# DotPhat.net
KiCad netlist of a schematic drawn in EAGLE
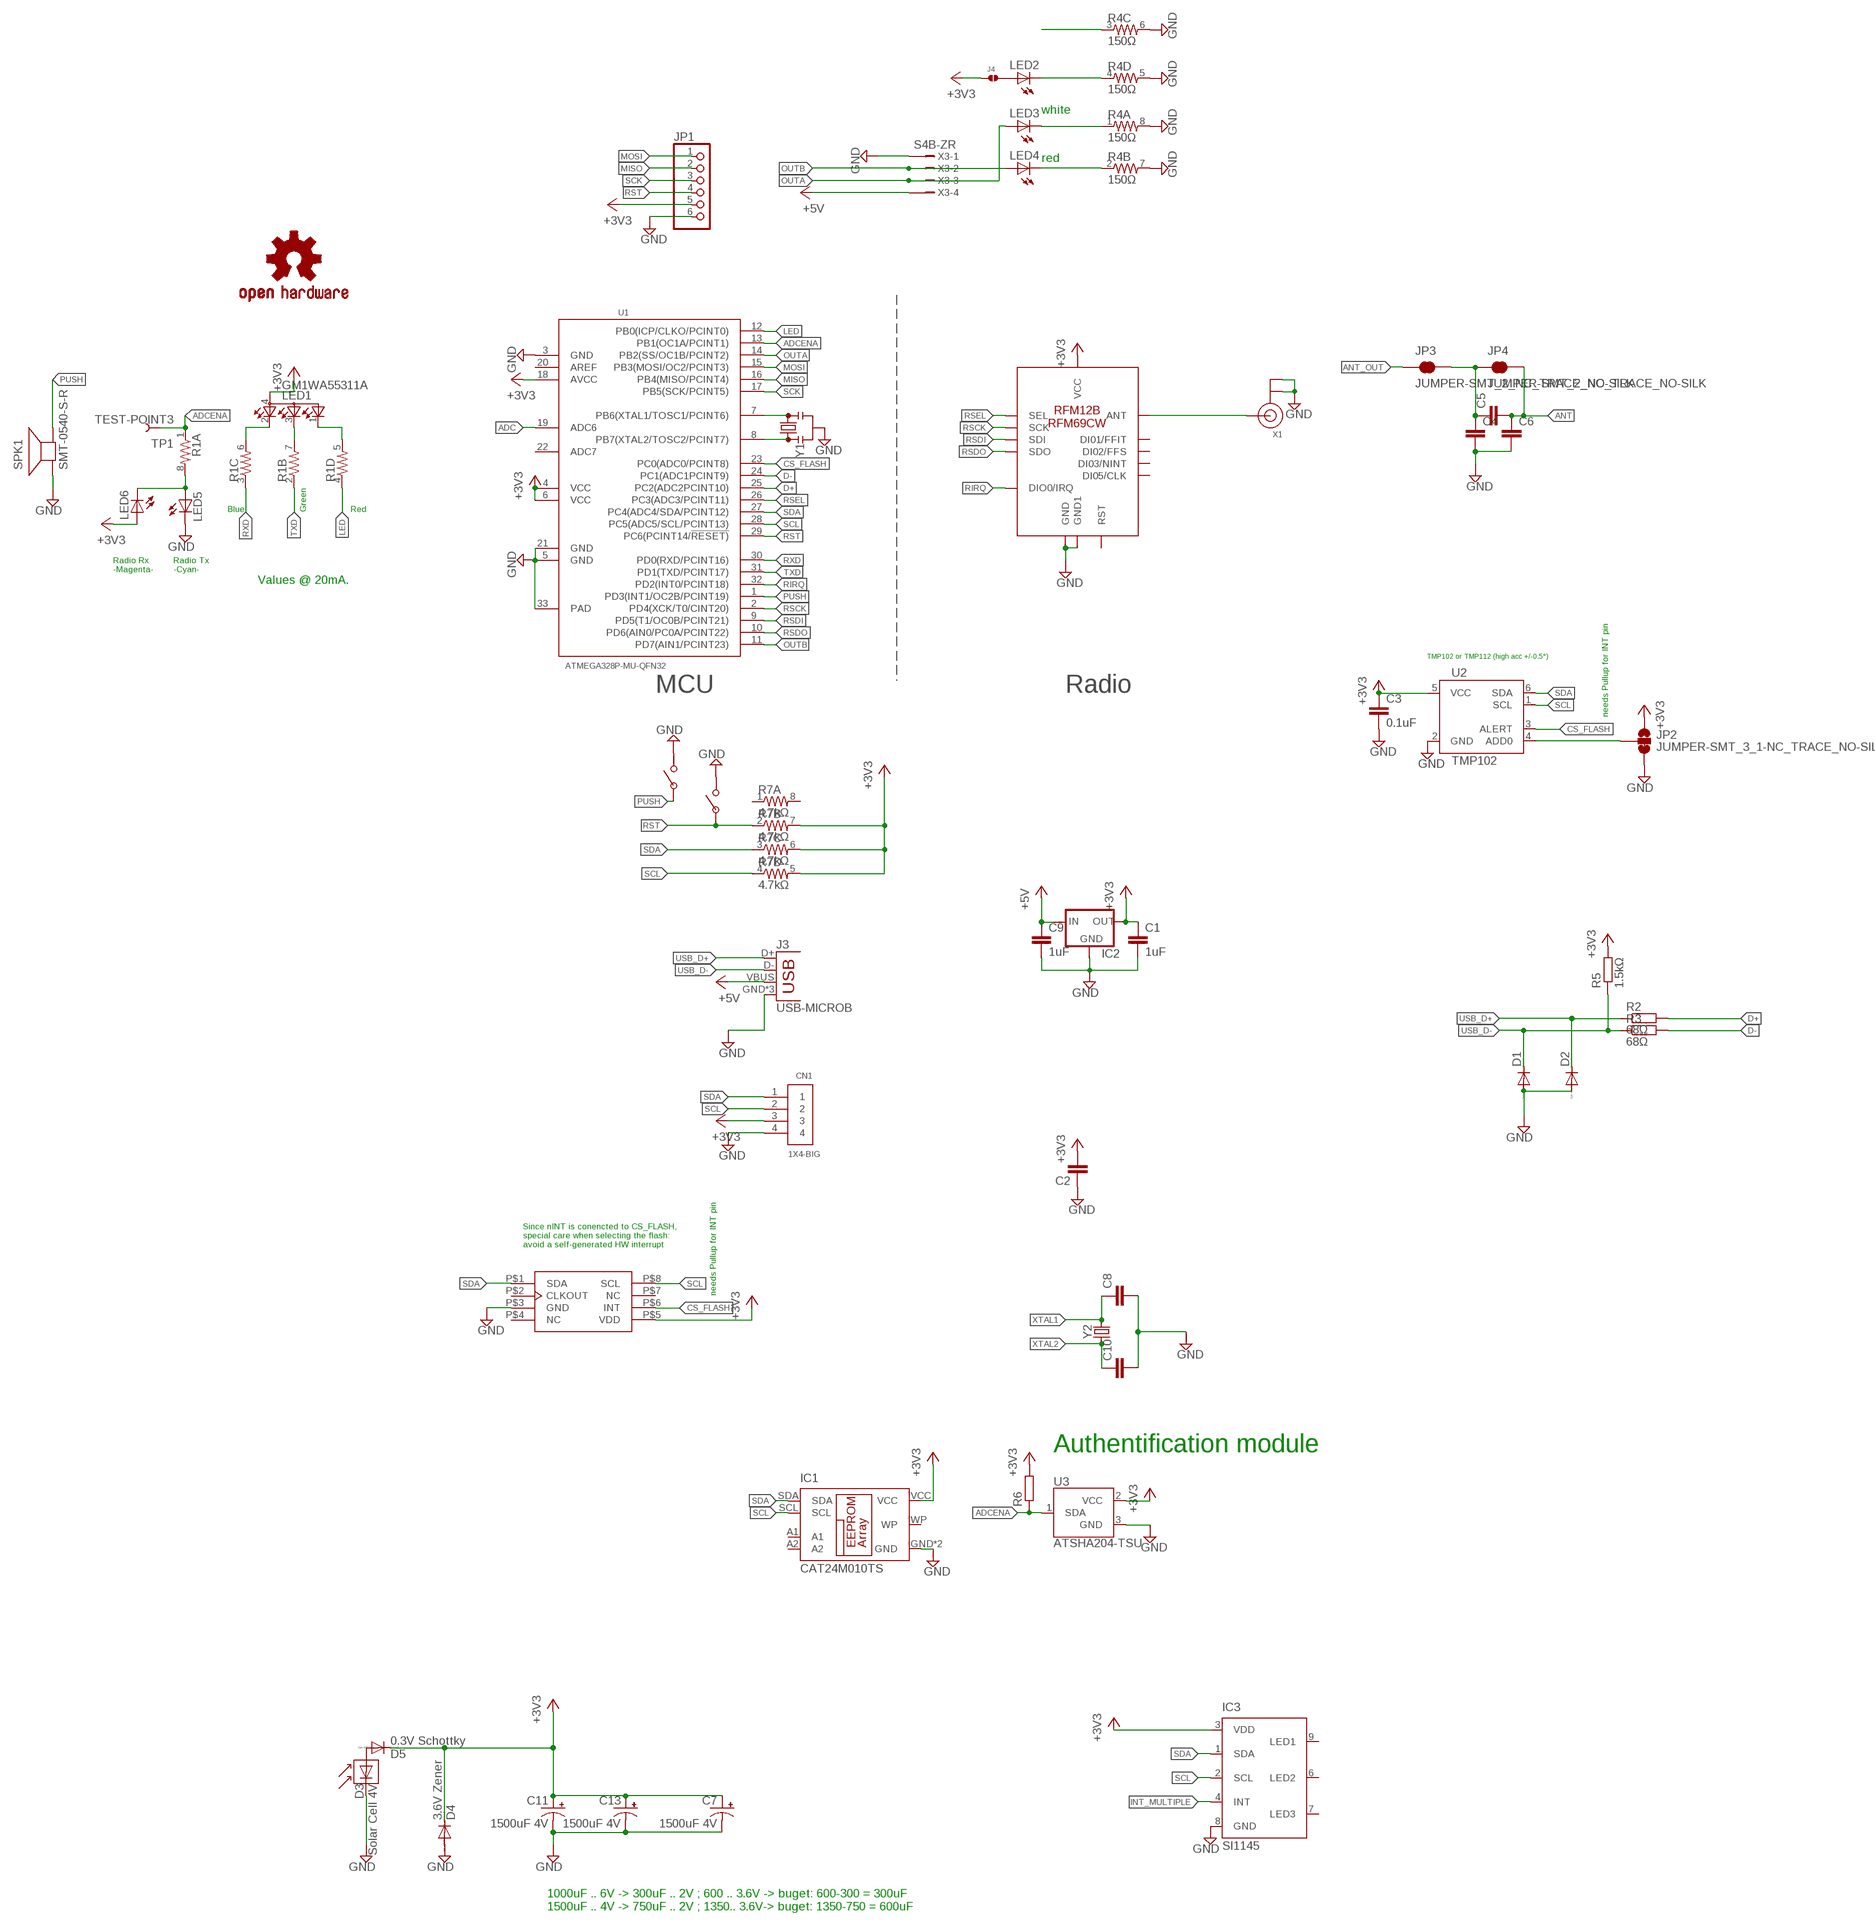
[diagram p0: schematic, sheet 1]

(export (version "E")
  (design (tool "Eeschema 10.0.6"))
  (components
    (comp (ref "C1")
      (value "1uF")
      (footprint "eagle-import:C0603")
      (libsource (lib "eagle-import") (part "C-EUC0603"))
    )
    (comp (ref "C2")
      (value "C-EUC3216")
      (footprint "eagle-import:C3216")
      (libsource (lib "eagle-import") (part "C-EUC3216"))
    )
    (comp (ref "C3")
      (value "0.1uF")
      (footprint "eagle-import:C0603")
      (libsource (lib "eagle-import") (part "resistor_C-EUC0603"))
    )
    (comp (ref "C4")
      (value "C-EUC0603")
      (footprint "eagle-import:C0603")
      (libsource (lib "eagle-import") (part "C-EUC0603"))
    )
    (comp (ref "C5")
      (value "C-EUC0603")
      (footprint "eagle-import:C0603")
      (libsource (lib "eagle-import") (part "C-EUC0603"))
    )
    (comp (ref "C6")
      (value "C-EUC0603")
      (footprint "eagle-import:C0603")
      (libsource (lib "eagle-import") (part "C-EUC0603"))
    )
    (comp (ref "C7")
      (value "1500uF 4V")
      (footprint "eagle-import:CT7343")
      (libsource (lib "eagle-import") (part "CPOL-USCT7343"))
    )
    (comp (ref "C8")
      (value "C-EUC0402")
      (footprint "eagle-import:C0402")
      (libsource (lib "eagle-import") (part "C-EUC0402"))
    )
    (comp (ref "C9")
      (value "1uF")
      (footprint "eagle-import:C0603")
      (libsource (lib "eagle-import") (part "C-EUC0603"))
    )
    (comp (ref "C10")
      (value "C-EUC0402")
      (footprint "eagle-import:C0402")
      (libsource (lib "eagle-import") (part "C-EUC0402"))
    )
    (comp (ref "C11")
      (value "1500uF 4V")
      (footprint "eagle-import:CT7343")
      (libsource (lib "eagle-import") (part "CPOL-USCT7343"))
    )
    (comp (ref "C13")
      (value "1500uF 4V")
      (footprint "eagle-import:CT7343")
      (libsource (lib "eagle-import") (part "CPOL-USCT7343"))
    )
    (comp (ref "CN1")
      (value "1X4-BIG")
      (footprint "eagle-import:1X04-BIG")
      (libsource (lib "eagle-import") (part "1X4-BIG"))
    )
    (comp (ref "D1")
      (value "DIODE-SOD523")
      (footprint "eagle-import:SOD523")
      (libsource (lib "eagle-import") (part "DIODE-SOD523"))
    )
    (comp (ref "D2")
      (value "DIODE-SOD523")
      (footprint "eagle-import:SOD523")
      (libsource (lib "eagle-import") (part "DIODE-SOD523"))
    )
    (comp (ref "D3")
      (value "Solar Cell 4V")
      (footprint "eagle-import:SOLARBIT-12X1")
      (libsource (lib "eagle-import") (part "SOLAR-IXYS-"))
    )
    (comp (ref "D4")
      (value "3.6V Zener")
      (footprint "eagle-import:SOD523")
      (libsource (lib "eagle-import") (part "DIODE-SOD523"))
    )
    (comp (ref "D5")
      (value "0.3V Schottky")
      (footprint "eagle-import:SOD523")
      (libsource (lib "eagle-import") (part "DIODE-SOD523"))
    )
    (comp (ref "IC1")
      (value "CAT24M010TS")
      (footprint "eagle-import:TSSOP8")
      (fields (field (name "MF") "On Semiconductor") (field (name "MPN") "24C00T-E/ST"))
      (libsource (lib "eagle-import") (part "CAT24M01TS0"))
    )
    (comp (ref "IC2")
      (value "MCP1700TT")
      (footprint "eagle-import:SOT-23")
      (libsource (lib "eagle-import") (part "MCP1700TT"))
    )
    (comp (ref "IC3")
      (value "SI1145")
      (footprint "eagle-import:QFN-10")
      (libsource (lib "eagle-import") (part "SI1145"))
    )
    (comp (ref "J3")
      (value "USB-MICROB")
      (footprint "eagle-import:USB-MICROB")
      (libsource (lib "eagle-import") (part "USB-MICROB"))
    )
    (comp (ref "J4")
      (value "SOLDERJUMPER.2.MED")
      (footprint "eagle-import:2.MED")
      (libsource (lib "eagle-import") (part "SOLDERJUMPER.2.MED"))
    )
    (comp (ref "JP1")
      (value "PINHD-1X6")
      (footprint "eagle-import:1X06")
      (libsource (lib "eagle-import") (part "PINHD-1X6"))
    )
    (comp (ref "JP2")
      (value "JUMPER-SMT_3_1-NC_TRACE_NO-SILK")
      (footprint "eagle-import:SMT-JUMPER_3_1-NC_TRACE_NO-SILK")
      (libsource (lib "eagle-import") (part "JUMPER-SMT_3_1-NC_TRACE_NO-SILK"))
    )
    (comp (ref "JP3")
      (value "JUMPER-SMT_2_NC_TRACE_NO-SILK")
      (footprint "eagle-import:SMT-JUMPER_2_NC_TRACE_NO-SILK")
      (libsource (lib "eagle-import") (part "JUMPER-SMT_2_NC_TRACE_NO-SILK"))
    )
    (comp (ref "JP4")
      (value "JUMPER-SMT_2_NC_TRACE_NO-SILK")
      (footprint "eagle-import:SMT-JUMPER_2_NC_TRACE_NO-SILK")
      (libsource (lib "eagle-import") (part "JUMPER-SMT_2_NC_TRACE_NO-SILK"))
    )
    (comp (ref "LED1")
      (value "GM1WA55311A")
      (footprint "eagle-import:GM1WA55311A")
      (libsource (lib "eagle-import") (part "GM1WA55311A"))
    )
    (comp (ref "LED2")
      (value "LED0603")
      (footprint "eagle-import:LED-0603")
      (libsource (lib "eagle-import") (part "LED0603"))
    )
    (comp (ref "LED3")
      (value "LED0603")
      (footprint "eagle-import:LED-0603")
      (libsource (lib "eagle-import") (part "LED0603"))
    )
    (comp (ref "LED4")
      (value "LED0603")
      (footprint "eagle-import:LED-0603")
      (libsource (lib "eagle-import") (part "LED0603"))
    )
    (comp (ref "LED5")
      (value "LED0603")
      (footprint "eagle-import:LED-0603")
      (libsource (lib "eagle-import") (part "LED0603"))
    )
    (comp (ref "LED6")
      (value "LED0603")
      (footprint "eagle-import:LED-0603")
      (libsource (lib "eagle-import") (part "LED0603"))
    )
    (comp (ref "LOGO1")
      (value "OSHW-LOGOS")
      (footprint "eagle-import:OSHW-LOGO-S")
      (libsource (lib "eagle-import") (part "OSHW-LOGOS"))
    )
    (comp (ref "R1")
      (value "RESISTOR-ARRAY0603-ARV")
      (footprint "eagle-import:0603-ARV")
      (libsource (lib "eagle-import") (part "RESISTOR-ARRAY0603-ARV"))
    )
    (comp (ref "R2")
      (value "68Ω")
      (footprint "eagle-import:R0603")
      (libsource (lib "eagle-import") (part "R-EU_R0603"))
    )
    (comp (ref "R3")
      (value "68Ω")
      (footprint "eagle-import:R0603")
      (libsource (lib "eagle-import") (part "R-EU_R0603"))
    )
    (comp (ref "R4")
      (value "150Ω")
      (footprint "eagle-import:0603-ARV")
      (libsource (lib "eagle-import") (part "RESISTOR-ARRAY0603-ARV"))
    )
    (comp (ref "R5")
      (value "1.5kΩ")
      (footprint "eagle-import:R0603")
      (libsource (lib "eagle-import") (part "R-EU_R0603"))
    )
    (comp (ref "R6")
      (value "R-EU_R0603")
      (footprint "eagle-import:R0603")
      (libsource (lib "eagle-import") (part "R-EU_R0603"))
    )
    (comp (ref "R7")
      (value "4.7kΩ")
      (footprint "eagle-import:0603-ARV")
      (libsource (lib "eagle-import") (part "RESISTOR-ARRAY0603-ARV"))
    )
    (comp (ref "SPK1")
      (value "SMT-0540-S-R")
      (footprint "eagle-import:SMT-0540-S-R")
      (libsource (lib "eagle-import") (part "SMT-0540-S-R"))
    )
    (comp (ref "TP1")
      (value "TEST-POINT3")
      (footprint "eagle-import:PAD.03X.03")
      (libsource (lib "eagle-import") (part "TEST-POINT3"))
    )
    (comp (ref "U$1")
      (value "RFM12B/69CW")
      (footprint "eagle-import:RFM12B_69CW")
      (libsource (lib "eagle-import") (part "RFM12B/69CW"))
    )
    (comp (ref "U$2")
      (value "PUSHBUTTON_4X2.5")
      (footprint "eagle-import:PUSHBUTTON_4X2.5")
      (libsource (lib "eagle-import") (part "PUSHBUTTON_4X2.5"))
    )
    (comp (ref "U$3")
      (value "PUSHBUTTON_4X2.5")
      (footprint "eagle-import:PUSHBUTTON_4X2.5")
      (libsource (lib "eagle-import") (part "PUSHBUTTON_4X2.5"))
    )
    (comp (ref "U1")
      (value "ATMEGA328P-MU-QFN32")
      (footprint "eagle-import:QFN32G-0.5-5X5MM")
      (fields (field (name "MPN") "ATMEGA328P-MU"))
      (libsource (lib "eagle-import") (part "MCU-ATMEGA328P-MU(QFN32)"))
    )
    (comp (ref "U2")
      (value "TMP102")
      (footprint "eagle-import:SOT563")
      (libsource (lib "eagle-import") (part "TMP102"))
    )
    (comp (ref "U3")
      (value "ATSHA204-TSU")
      (footprint "eagle-import:SOT23-3")
      (libsource (lib "eagle-import") (part "ATSHA204-TSU"))
    )
    (comp (ref "X1")
      (value "ANTENNA_U.FL")
      (footprint "eagle-import:U.FL")
      (libsource (lib "eagle-import") (part "ANTENNA_U.FL"))
    )
    (comp (ref "X2")
      (value "MC-RTC-RV-4162-C7-I2C")
      (footprint "eagle-import:MC-RTC-C7")
      (libsource (lib "eagle-import") (part "MC-RTC-RV-4162-C7-I2C"))
    )
    (comp (ref "X3")
      (value "S4B-ZR")
      (footprint "eagle-import:S4B-ZR")
      (fields (field (name "MF") "FARNELL") (field (name "MPN") "S4B-ZR(LF)(SN)"))
      (libsource (lib "eagle-import") (part "?4B-ZRS"))
    )
    (comp (ref "Y1")
      (value "RESONATORSMD-3.2X1.3")
      (footprint "eagle-import:RESONATOR-SMD-3.2X1.3")
      (libsource (lib "eagle-import") (part "RESONATORSMD-3.2X1.3"))
    )
    (comp (ref "Y2")
      (value "CRYSTALSMD-3.2X1.5")
      (footprint "eagle-import:CRYSTAL-SMD-3.2X1.5MM")
      (libsource (lib "eagle-import") (part "CRYSTALSMD-3.2X1.5"))
    )
  )
  (nets
    (net (code "1") (name "+3V3") (class "Default")
      (node (ref "C1") (pin "1") (pinfunction "1_1") (pintype "passive"))
      (node (ref "C11") (pin "+") (pinfunction "+_+") (pintype "passive"))
      (node (ref "C13") (pin "+") (pinfunction "+_+") (pintype "passive"))
      (node (ref "C2") (pin "2") (pinfunction "2_2") (pintype "passive"))
      (node (ref "C3") (pin "1") (pinfunction "1_1") (pintype "passive"))
      (node (ref "C7") (pin "+") (pinfunction "+_+") (pintype "passive"))
      (node (ref "CN1") (pin "3") (pinfunction "3_3") (pintype "bidirectional"))
      (node (ref "D4") (pin "C") (pinfunction "C_C") (pintype "passive"))
      (node (ref "D5") (pin "C") (pinfunction "C_C") (pintype "passive"))
      (node (ref "IC1") (pin "VCC") (pinfunction "VCC_VCC") (pintype "power_in"))
      (node (ref "IC2") (pin "2") (pinfunction "OUT_2") (pintype "passive"))
      (node (ref "IC3") (pin "3") (pinfunction "VDD_3") (pintype "power_in"))
      (node (ref "J4") (pin "1") (pinfunction "1_1") (pintype "bidirectional"))
      (node (ref "JP1") (pin "5") (pinfunction "5_5") (pintype "passive"))
      (node (ref "JP2") (pin "1") (pinfunction "1_1") (pintype "passive"))
      (node (ref "LED1") (pin "4") (pinfunction "A_4") (pintype "passive"))
      (node (ref "LED6") (pin "A") (pinfunction "A_A") (pintype "passive"))
      (node (ref "R5") (pin "2") (pinfunction "2_2") (pintype "passive"))
      (node (ref "R6") (pin "2") (pinfunction "2_2") (pintype "passive"))
      (node (ref "R7") (pin "5") (pinfunction "2_5") (pintype "passive"))
      (node (ref "R7") (pin "6") (pinfunction "2_6") (pintype "passive"))
      (node (ref "R7") (pin "7") (pinfunction "2_7") (pintype "passive"))
      (node (ref "U$1") (pin "VDD") (pinfunction "VCC_VDD") (pintype "power_in"))
      (node (ref "U1") (pin "18") (pinfunction "AVCC_18") (pintype "bidirectional"))
      (node (ref "U1") (pin "4") (pinfunction "VCC_4") (pintype "bidirectional"))
      (node (ref "U1") (pin "6") (pinfunction "VCC_6") (pintype "bidirectional"))
      (node (ref "U2") (pin "5") (pinfunction "VCC_5") (pintype "bidirectional"))
      (node (ref "U3") (pin "2") (pinfunction "VCC_2") (pintype "bidirectional"))
      (node (ref "X2") (pin "P$5") (pinfunction "VDD_P$5") (pintype "power_in"))
    )
    (net (code "2") (name "+5V") (class "Default")
      (node (ref "C9") (pin "1") (pinfunction "1_1") (pintype "passive"))
      (node (ref "IC2") (pin "3") (pinfunction "IN_3") (pintype "input"))
      (node (ref "J3") (pin "VBUS") (pinfunction "VBUS_VBUS") (pintype "bidirectional"))
      (node (ref "X3") (pin "4") (pinfunction "1_4") (pintype "passive"))
    )
    (net (code "3") (name "ADC") (class "Default")
      (node (ref "U1") (pin "19") (pinfunction "ADC6_19") (pintype "bidirectional"))
    )
    (net (code "4") (name "ADCENA") (class "Default")
      (node (ref "R1") (pin "1") (pinfunction "1_1") (pintype "passive"))
      (node (ref "R6") (pin "1") (pinfunction "1_1") (pintype "passive"))
      (node (ref "TP1") (pin "P$1") (pinfunction "1_P$1") (pintype "bidirectional"))
      (node (ref "U1") (pin "13") (pinfunction "PB1(OC1A/PCINT1)_13") (pintype "bidirectional"))
      (node (ref "U3") (pin "1") (pinfunction "SDA_1") (pintype "bidirectional"))
    )
    (net (code "5") (name "ANT") (class "Default")
      (node (ref "C5") (pin "2") (pinfunction "2_2") (pintype "passive"))
      (node (ref "C6") (pin "1") (pinfunction "1_1") (pintype "passive"))
      (node (ref "JP4") (pin "2") (pinfunction "2_2") (pintype "passive"))
    )
    (net (code "6") (name "ANT_OUT") (class "Default")
      (node (ref "JP3") (pin "1") (pinfunction "1_1") (pintype "passive"))
      (node (ref "U$1") (pin "ANT") (pinfunction "ANT_ANT") (pintype "passive"))
      (node (ref "X1") (pin "3") (pinfunction "SIGNAL_3") (pintype "passive"))
    )
    (net (code "7") (name "CS_FLASH") (class "Default")
      (node (ref "U1") (pin "23") (pinfunction "PC0(ADC0/PCINT8)_23") (pintype "bidirectional"))
      (node (ref "U2") (pin "3") (pinfunction "ALERT_3") (pintype "bidirectional"))
      (node (ref "X2") (pin "P$6") (pinfunction "INT_P$6") (pintype "bidirectional"))
    )
    (net (code "8") (name "D+") (class "Default")
      (node (ref "R2") (pin "2") (pinfunction "2_2") (pintype "passive"))
      (node (ref "U1") (pin "25") (pinfunction "PC2(ADC2PCINT10)_25") (pintype "bidirectional"))
    )
    (net (code "9") (name "D-") (class "Default")
      (node (ref "R3") (pin "2") (pinfunction "2_2") (pintype "passive"))
      (node (ref "U1") (pin "24") (pinfunction "PC1(ADC1PCINT9)_24") (pintype "bidirectional"))
    )
    (net (code "10") (name "GND") (class "Default")
      (node (ref "C1") (pin "2") (pinfunction "2_2") (pintype "passive"))
      (node (ref "C10") (pin "2") (pinfunction "2_2") (pintype "passive"))
      (node (ref "C11") (pin "-") (pinfunction "-_-") (pintype "passive"))
      (node (ref "C13") (pin "-") (pinfunction "-_-") (pintype "passive"))
      (node (ref "C2") (pin "1") (pinfunction "1_1") (pintype "passive"))
      (node (ref "C3") (pin "2") (pinfunction "2_2") (pintype "passive"))
      (node (ref "C4") (pin "2") (pinfunction "2_2") (pintype "passive"))
      (node (ref "C6") (pin "2") (pinfunction "2_2") (pintype "passive"))
      (node (ref "C7") (pin "-") (pinfunction "-_-") (pintype "passive"))
      (node (ref "C8") (pin "2") (pinfunction "2_2") (pintype "passive"))
      (node (ref "C9") (pin "2") (pinfunction "2_2") (pintype "passive"))
      (node (ref "CN1") (pin "4") (pinfunction "4_4") (pintype "bidirectional"))
      (node (ref "D1") (pin "A") (pinfunction "A_A") (pintype "passive"))
      (node (ref "D2") (pin "A") (pinfunction "A_A") (pintype "passive"))
      (node (ref "D3") (pin "-") (pinfunction "C_-") (pintype "passive"))
      (node (ref "D4") (pin "A") (pinfunction "A_A") (pintype "passive"))
      (node (ref "IC1") (pin "GND") (pinfunction "GND_GND") (pintype "power_in"))
      (node (ref "IC1") (pin "NC") (pinfunction "GND_NC") (pintype "power_in"))
      (node (ref "IC2") (pin "1") (pinfunction "GND_1") (pintype "input"))
      (node (ref "IC3") (pin "8") (pinfunction "GND_8") (pintype "power_in"))
      (node (ref "J3") (pin "GND") (pinfunction "GND_GND") (pintype "bidirectional"))
      (node (ref "J3") (pin "MT1") (pinfunction "GND_MT1") (pintype "bidirectional"))
      (node (ref "J3") (pin "MT2") (pinfunction "GND_MT2") (pintype "bidirectional"))
      (node (ref "JP1") (pin "6") (pinfunction "6_6") (pintype "passive"))
      (node (ref "JP2") (pin "3") (pinfunction "3_3") (pintype "passive"))
      (node (ref "LED5") (pin "C") (pinfunction "C_C") (pintype "passive"))
      (node (ref "R4") (pin "5") (pinfunction "2_5") (pintype "passive"))
      (node (ref "R4") (pin "6") (pinfunction "2_6") (pintype "passive"))
      (node (ref "R4") (pin "7") (pinfunction "2_7") (pintype "passive"))
      (node (ref "R4") (pin "8") (pinfunction "2_8") (pintype "passive"))
      (node (ref "SPK1") (pin "-") (pinfunction "+_-") (pintype "passive"))
      (node (ref "U$1") (pin "GND") (pinfunction "GND_GND") (pintype "power_in"))
      (node (ref "U$1") (pin "GND1") (pinfunction "GND1_GND1") (pintype "power_in"))
      (node (ref "U$2") (pin "P$2") (pinfunction "P$2_P$2") (pintype "bidirectional"))
      (node (ref "U$3") (pin "P$2") (pinfunction "P$2_P$2") (pintype "bidirectional"))
      (node (ref "U1") (pin "21") (pinfunction "GND_21") (pintype "bidirectional"))
      (node (ref "U1") (pin "3") (pinfunction "GND_3") (pintype "bidirectional"))
      (node (ref "U1") (pin "33") (pinfunction "PAD_33") (pintype "bidirectional"))
      (node (ref "U1") (pin "5") (pinfunction "GND_5") (pintype "bidirectional"))
      (node (ref "U2") (pin "2") (pinfunction "GND_2") (pintype "bidirectional"))
      (node (ref "U3") (pin "3") (pinfunction "GND_3") (pintype "bidirectional"))
      (node (ref "X1") (pin "1") (pinfunction "GND_1") (pintype "passive"))
      (node (ref "X1") (pin "2") (pinfunction "GND_2") (pintype "passive"))
      (node (ref "X2") (pin "P$3") (pinfunction "GND_P$3") (pintype "power_in"))
      (node (ref "X3") (pin "1") (pinfunction "1_1") (pintype "passive"))
      (node (ref "Y1") (pin "2") (pinfunction "2_2") (pintype "passive"))
    )
    (net (code "11") (name "INT_MULTIPLE") (class "Default")
      (node (ref "IC3") (pin "4") (pinfunction "INT_4") (pintype "open_collector"))
    )
    (net (code "12") (name "LED") (class "Default")
      (node (ref "R1") (pin "4") (pinfunction "1_4") (pintype "passive"))
      (node (ref "U1") (pin "12") (pinfunction "PB0(ICP/CLKO/PCINT0)_12") (pintype "bidirectional"))
    )
    (net (code "13") (name "MISO") (class "Default")
      (node (ref "JP1") (pin "2") (pinfunction "2_2") (pintype "passive"))
      (node (ref "U1") (pin "16") (pinfunction "PB4(MISO/PCINT4)_16") (pintype "bidirectional"))
    )
    (net (code "14") (name "MOSI") (class "Default")
      (node (ref "JP1") (pin "1") (pinfunction "1_1") (pintype "passive"))
      (node (ref "U1") (pin "15") (pinfunction "PB3(MOSI/OC2/PCINT3)_15") (pintype "bidirectional"))
    )
    (net (code "15") (name "Net-(C4-Pad1)") (class "Default")
      (node (ref "C4") (pin "1") (pinfunction "1_1") (pintype "passive"))
      (node (ref "C5") (pin "1") (pinfunction "1_1") (pintype "passive"))
      (node (ref "JP3") (pin "2") (pinfunction "2_2") (pintype "passive"))
      (node (ref "JP4") (pin "1") (pinfunction "1_1") (pintype "passive"))
    )
    (net (code "16") (name "Net-(D3-A)") (class "Default")
      (node (ref "D3") (pin "+") (pinfunction "A_+") (pintype "passive"))
      (node (ref "D5") (pin "A") (pinfunction "A_A") (pintype "passive"))
    )
    (net (code "17") (name "Net-(J4-Pad2)") (class "Default")
      (node (ref "J4") (pin "2") (pinfunction "2_2") (pintype "bidirectional"))
      (node (ref "LED2") (pin "A") (pinfunction "A_A") (pintype "passive"))
    )
    (net (code "18") (name "Net-(LED1-CBLUE)") (class "Default")
      (node (ref "LED1") (pin "3") (pinfunction "CBLUE_3") (pintype "passive"))
      (node (ref "R1") (pin "7") (pinfunction "2_7") (pintype "passive"))
    )
    (net (code "19") (name "Net-(LED1-CGREEN)") (class "Default")
      (node (ref "LED1") (pin "1") (pinfunction "CGREEN_1") (pintype "passive"))
      (node (ref "R1") (pin "5") (pinfunction "2_5") (pintype "passive"))
    )
    (net (code "20") (name "Net-(LED1-CRED)") (class "Default")
      (node (ref "LED1") (pin "2") (pinfunction "CRED_2") (pintype "passive"))
      (node (ref "R1") (pin "6") (pinfunction "2_6") (pintype "passive"))
    )
    (net (code "21") (name "Net-(LED3-PadC)") (class "Default")
      (node (ref "LED3") (pin "C") (pinfunction "C_C") (pintype "passive"))
      (node (ref "R4") (pin "1") (pinfunction "1_1") (pintype "passive"))
    )
    (net (code "22") (name "Net-(R1A-2)") (class "Default")
      (node (ref "LED5") (pin "A") (pinfunction "A_A") (pintype "passive"))
      (node (ref "LED6") (pin "C") (pinfunction "C_C") (pintype "passive"))
      (node (ref "R1") (pin "8") (pinfunction "2_8") (pintype "passive"))
    )
    (net (code "23") (name "Net-(R4B-1)") (class "Default")
      (node (ref "LED4") (pin "C") (pinfunction "C_C") (pintype "passive"))
      (node (ref "R4") (pin "2") (pinfunction "1_2") (pintype "passive"))
    )
    (net (code "24") (name "Net-(R4D-1)") (class "Default")
      (node (ref "LED2") (pin "C") (pinfunction "C_C") (pintype "passive"))
      (node (ref "R4") (pin "4") (pinfunction "1_4") (pintype "passive"))
    )
    (net (code "25") (name "Net-(U1-PB6(XTAL1{slash}TOSC1{slash}PCINT6))") (class "Default")
      (node (ref "U1") (pin "7") (pinfunction "PB6(XTAL1/TOSC1/PCINT6)_7") (pintype "bidirectional"))
      (node (ref "Y1") (pin "3") (pinfunction "3_3") (pintype "passive"))
    )
    (net (code "26") (name "Net-(U1-PB7(XTAL2{slash}TOSC2{slash}PCINT7))") (class "Default")
      (node (ref "U1") (pin "8") (pinfunction "PB7(XTAL2/TOSC2/PCINT7)_8") (pintype "bidirectional"))
      (node (ref "Y1") (pin "1") (pinfunction "1_1") (pintype "passive"))
    )
    (net (code "27") (name "Net-(U2-ADD0)") (class "Default")
      (node (ref "JP2") (pin "2") (pinfunction "2_2") (pintype "passive"))
      (node (ref "U2") (pin "4") (pinfunction "ADD0_4") (pintype "bidirectional"))
    )
    (net (code "28") (name "OUTA") (class "Default")
      (node (ref "LED3") (pin "A") (pinfunction "A_A") (pintype "passive"))
      (node (ref "U1") (pin "14") (pinfunction "PB2(SS/OC1B/PCINT2)_14") (pintype "bidirectional"))
      (node (ref "X3") (pin "3") (pinfunction "1_3") (pintype "passive"))
    )
    (net (code "29") (name "OUTB") (class "Default")
      (node (ref "LED4") (pin "A") (pinfunction "A_A") (pintype "passive"))
      (node (ref "U1") (pin "11") (pinfunction "PD7(AIN1/PCINT23)_11") (pintype "bidirectional"))
      (node (ref "X3") (pin "2") (pinfunction "1_2") (pintype "passive"))
    )
    (net (code "30") (name "PUSH") (class "Default")
      (node (ref "SPK1") (pin "+") (pinfunction "-_+") (pintype "passive"))
      (node (ref "U$3") (pin "P$1") (pinfunction "P$1_P$1") (pintype "bidirectional"))
      (node (ref "U1") (pin "1") (pinfunction "PD3(INT1/OC2B/PCINT19)_1") (pintype "bidirectional"))
    )
    (net (code "31") (name "RIRQ") (class "Default")
      (node (ref "U$1") (pin "IRQ") (pinfunction "DIO0/IRQ_IRQ") (pintype "open_collector"))
      (node (ref "U1") (pin "32") (pinfunction "PD2(INT0/PCINT18)_32") (pintype "bidirectional"))
    )
    (net (code "32") (name "RSCK") (class "Default")
      (node (ref "U$1") (pin "SCK") (pinfunction "SCK_SCK") (pintype "input"))
      (node (ref "U1") (pin "2") (pinfunction "PD4(XCK/T0/CINT20)_2") (pintype "bidirectional"))
    )
    (net (code "33") (name "RSDI") (class "Default")
      (node (ref "U$1") (pin "SDI") (pinfunction "SDI_SDI") (pintype "input"))
      (node (ref "U1") (pin "9") (pinfunction "PD5(T1/OC0B/PCINT21)_9") (pintype "bidirectional"))
    )
    (net (code "34") (name "RSDO") (class "Default")
      (node (ref "U$1") (pin "SDO") (pinfunction "SDO_SDO") (pintype "output"))
      (node (ref "U1") (pin "10") (pinfunction "PD6(AIN0/PC0A/PCINT22)_10") (pintype "bidirectional"))
    )
    (net (code "35") (name "RSEL") (class "Default")
      (node (ref "U$1") (pin "SEL") (pinfunction "SEL_SEL") (pintype "input"))
      (node (ref "U1") (pin "26") (pinfunction "PC3(ADC3/PCINT11)_26") (pintype "bidirectional"))
    )
    (net (code "36") (name "RST") (class "Default")
      (node (ref "JP1") (pin "4") (pinfunction "4_4") (pintype "passive"))
      (node (ref "R7") (pin "2") (pinfunction "1_2") (pintype "passive"))
      (node (ref "U$2") (pin "P$1") (pinfunction "P$1_P$1") (pintype "bidirectional"))
      (node (ref "U1") (pin "29") (pinfunction "PC6(PCINT14/~{RESET})_29") (pintype "bidirectional"))
    )
    (net (code "37") (name "RXD") (class "Default")
      (node (ref "R1") (pin "3") (pinfunction "1_3") (pintype "passive"))
      (node (ref "U1") (pin "30") (pinfunction "PD0(RXD/PCINT16)_30") (pintype "bidirectional"))
    )
    (net (code "38") (name "SCK") (class "Default")
      (node (ref "JP1") (pin "3") (pinfunction "3_3") (pintype "passive"))
      (node (ref "U1") (pin "17") (pinfunction "PB5(SCK/PCINT5)_17") (pintype "bidirectional"))
    )
    (net (code "39") (name "SCL") (class "Default")
      (node (ref "CN1") (pin "2") (pinfunction "2_2") (pintype "bidirectional"))
      (node (ref "IC1") (pin "SCL") (pinfunction "SCL_SCL") (pintype "input"))
      (node (ref "IC3") (pin "2") (pinfunction "SCL_2") (pintype "input"))
      (node (ref "R7") (pin "4") (pinfunction "1_4") (pintype "passive"))
      (node (ref "U1") (pin "28") (pinfunction "PC5(ADC5/SCL/PCINT13)_28") (pintype "bidirectional"))
      (node (ref "U2") (pin "1") (pinfunction "SCL_1") (pintype "bidirectional"))
      (node (ref "X2") (pin "P$8") (pinfunction "SCL_P$8") (pintype "bidirectional"))
    )
    (net (code "40") (name "SDA") (class "Default")
      (node (ref "CN1") (pin "1") (pinfunction "1_1") (pintype "bidirectional"))
      (node (ref "IC1") (pin "SDA") (pinfunction "SDA_SDA") (pintype "bidirectional"))
      (node (ref "IC3") (pin "1") (pinfunction "SDA_1") (pintype "bidirectional"))
      (node (ref "R7") (pin "3") (pinfunction "1_3") (pintype "passive"))
      (node (ref "U1") (pin "27") (pinfunction "PC4(ADC4/SDA/PCINT12)_27") (pintype "bidirectional"))
      (node (ref "U2") (pin "6") (pinfunction "SDA_6") (pintype "bidirectional"))
      (node (ref "X2") (pin "P$1") (pinfunction "SDA_P$1") (pintype "bidirectional"))
    )
    (net (code "41") (name "TXD") (class "Default")
      (node (ref "R1") (pin "2") (pinfunction "1_2") (pintype "passive"))
      (node (ref "U1") (pin "31") (pinfunction "PD1(TXD/PCINT17)_31") (pintype "bidirectional"))
    )
    (net (code "42") (name "USB_D+") (class "Default")
      (node (ref "D2") (pin "C") (pinfunction "C_C") (pintype "passive"))
      (node (ref "J3") (pin "D+") (pinfunction "D+_D+") (pintype "bidirectional"))
      (node (ref "R2") (pin "1") (pinfunction "1_1") (pintype "passive"))
    )
    (net (code "43") (name "USB_D-") (class "Default")
      (node (ref "D1") (pin "C") (pinfunction "C_C") (pintype "passive"))
      (node (ref "J3") (pin "D-") (pinfunction "D-_D-") (pintype "bidirectional"))
      (node (ref "R3") (pin "1") (pinfunction "1_1") (pintype "passive"))
      (node (ref "R5") (pin "1") (pinfunction "1_1") (pintype "passive"))
    )
    (net (code "44") (name "XTAL1") (class "Default")
      (node (ref "C8") (pin "1") (pinfunction "1_1") (pintype "passive"))
      (node (ref "Y2") (pin "P$2") (pinfunction "2_P$2") (pintype "passive"))
    )
    (net (code "45") (name "XTAL2") (class "Default")
      (node (ref "C10") (pin "1") (pinfunction "1_1") (pintype "passive"))
      (node (ref "Y2") (pin "P$1") (pinfunction "1_P$1") (pintype "passive"))
    )
    (net (code "46") (name "unconnected-(IC1-PadA1)") (class "Default")
      (node (ref "IC1") (pin "A1") (pinfunction "A1_A1") (pintype "bidirectional"))
    )
    (net (code "47") (name "unconnected-(IC1-PadA2)") (class "Default")
      (node (ref "IC1") (pin "A2") (pinfunction "A2_A2") (pintype "bidirectional"))
    )
    (net (code "48") (name "unconnected-(IC1-PadWP)") (class "Default")
      (node (ref "IC1") (pin "WP") (pinfunction "WP_WP") (pintype "bidirectional"))
    )
    (net (code "49") (name "unconnected-(IC3-LED1-Pad9)") (class "Default")
      (node (ref "IC3") (pin "9") (pinfunction "LED1_9") (pintype "output"))
    )
    (net (code "50") (name "unconnected-(IC3-LED2-Pad6)") (class "Default")
      (node (ref "IC3") (pin "6") (pinfunction "LED2_6") (pintype "output"))
    )
    (net (code "51") (name "unconnected-(IC3-LED3-Pad7)") (class "Default")
      (node (ref "IC3") (pin "7") (pinfunction "LED3_7") (pintype "output"))
    )
    (net (code "52") (name "unconnected-(R4C-1-Pad3)") (class "Default")
      (node (ref "R4") (pin "3") (pinfunction "1_3") (pintype "passive"))
    )
    (net (code "53") (name "unconnected-(R7-Pad1)") (class "Default")
      (node (ref "R7") (pin "1") (pinfunction "1_1") (pintype "passive"))
    )
    (net (code "54") (name "unconnected-(R7A-2-Pad8)") (class "Default")
      (node (ref "R7") (pin "8") (pinfunction "2_8") (pintype "passive"))
    )
    (net (code "55") (name "unconnected-(U$1-DI01{slash}FFIT-PadFFIT)") (class "Default")
      (node (ref "U$1") (pin "FFIT") (pinfunction "DI01/FFIT_FFIT") (pintype "passive"))
    )
    (net (code "56") (name "unconnected-(U$1-DI02{slash}FFS-PadFFS)") (class "Default")
      (node (ref "U$1") (pin "FFS") (pinfunction "DI02/FFS_FFS") (pintype "bidirectional"))
    )
    (net (code "57") (name "unconnected-(U$1-DI03{slash}NINT-PadNINT)") (class "Default")
      (node (ref "U$1") (pin "NINT") (pinfunction "DI03/NINT_NINT") (pintype "passive"))
    )
    (net (code "58") (name "unconnected-(U$1-DI05{slash}CLK-PadCLK)") (class "Default")
      (node (ref "U$1") (pin "CLK") (pinfunction "DI05/CLK_CLK") (pintype "passive"))
    )
    (net (code "59") (name "unconnected-(U$1-PadRST)") (class "Default")
      (node (ref "U$1") (pin "RST") (pinfunction "RST_RST") (pintype "open_collector"))
    )
    (net (code "60") (name "unconnected-(U1-ADC7-Pad22)") (class "Default")
      (node (ref "U1") (pin "22") (pinfunction "ADC7_22") (pintype "bidirectional"))
    )
    (net (code "61") (name "unconnected-(U1-AREF-Pad20)") (class "Default")
      (node (ref "U1") (pin "20") (pinfunction "AREF_20") (pintype "bidirectional"))
    )
    (net (code "62") (name "unconnected-(X2-CLKOUT-PadP$2)") (class "Default")
      (node (ref "X2") (pin "P$2") (pinfunction "CLKOUT_P$2") (pintype "bidirectional"))
    )
    (net (code "63") (name "unconnected-(X2-NC-PadP$4)") (class "Default")
      (node (ref "X2") (pin "P$4") (pinfunction "NC_P$4") (pintype "no_connect"))
    )
    (net (code "64") (name "unconnected-(X2-NC-PadP$7)") (class "Default")
      (node (ref "X2") (pin "P$7") (pinfunction "NC_P$7") (pintype "no_connect"))
    )
  )
)
